# Buzzer.net
KiCad netlist of a schematic drawn in Altium Designer
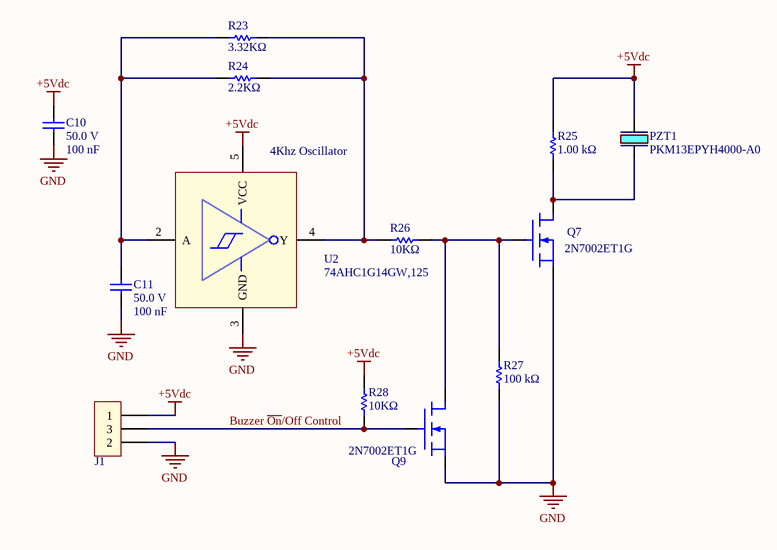
[diagram p0: Buzzer.SchDoc]

(export (version "E")
  (design (tool "Eeschema 10.0.6"))
  (components
    (comp (ref "C10")
      (value "08055C104JAT2A")
      (footprint "Cap,0805")
      (description "Capacitor; Ceramic; Cap 0.1 uF; Tol 5%; Vol-Rtg 50 VDC; SMT; 0805; X7R; Tape & Reel")
      (fields (field (name "VOLTAGE RATING (DC)") "50.0 V") (field (name "CAPACITANCE") "100 nF"))
      (libsource (lib "Master Mar2021") (part "Cap,0805,100nf,50V,5%,08055C104JAT2A"))
    )
    (comp (ref "C11")
      (value "08055C104JAT2A")
      (footprint "Cap,0805")
      (description "Capacitor; Ceramic; Cap 0.1 uF; Tol 5%; Vol-Rtg 50 VDC; SMT; 0805; X7R; Tape & Reel")
      (fields (field (name "VOLTAGE RATING (DC)") "50.0 V") (field (name "CAPACITANCE") "100 nF"))
      (libsource (lib "Master Mar2021") (part "Cap,0805,100nf,50V,5%,08055C104JAT2A"))
    )
    (comp (ref "J1")
      (value "Generic Header")
      (footprint "Header,3POS,0.1\",RA")
      (description "Generic Header 3 pos header 0.1\"")
      (libsource (lib "Master DEC 2020") (part "Header 1x3,0.1{dblquote},TH,Generic"))
    )
    (comp (ref "PZT1")
      (value "PKM13EPYH4000-A0")
      (footprint "Buzzer,PKM13EPYH4000-A0")
      (description "AUDIO PIEZO TRANSDUCER 30V TH")
      (fields (field (name "MANUFACTURER") "Murata Electronics"))
      (libsource (lib "Master Mar2021") (part "Buzzer,PIEZO,30V,TH,4Khz,PKM13EPYH4000-A0"))
    )
    (comp (ref "Q7")
      (value "2N7002ET1G")
      (footprint "SOT23-3")
      (description "Small Signal MOSFET, 60 V, 310 mA, Single, N-Channel, 3-Pin SOT-23, Pb-Free, Tape and Reel")
      (fields
        (field (name "MANUFACTURER") "ON Semiconductor")
        (field (name "MANUFACTURER PART NUMBER") "2N7002ET1G")
      )
      (libsource (lib "Master Mar2021") (part "MOSFET,N-Channel,SOT23,0.25A,60V,2N7002ET1G"))
    )
    (comp (ref "Q9")
      (value "2N7002ET1G")
      (footprint "SOT23-3")
      (description "Small Signal MOSFET, 60 V, 310 mA, Single, N-Channel, 3-Pin SOT-23, Pb-Free, Tape and Reel")
      (fields
        (field (name "MANUFACTURER") "ON Semiconductor")
        (field (name "MANUFACTURER PART NUMBER") "2N7002ET1G")
      )
      (libsource (lib "Master Mar2021") (part "MOSFET,N-Channel,SOT23,0.25A,60V,2N7002ET1G"))
    )
    (comp (ref "R23")
      (value "CRCW08053K32FKEA")
      (footprint "res, 0805, HD")
      (description "RES SMD 3.32K OHM 1% 1/8W 0805")
      (fields (field (name "RESISTANCE") "3.32KΩ"))
      (libsource (lib "Master Mar2021") (part "Res,0805,3.32K,±1%,100.0 ppm/°C,150.0 V,CRCW08053K32FKEA"))
    )
    (comp (ref "R24")
      (value "CRCW08052K20FKEA")
      (footprint "res, 0805, HD")
      (description "RES SMD 2.2K OHM 1% 1/8W 0805")
      (fields (field (name "RESISTANCE") "2.2KΩ"))
      (libsource (lib "Master Mar2021") (part "Res,0805,2.2KΩ,±1%,100.0 ppm/°C,150.0 V,CRCW08052K20FKEA"))
    )
    (comp (ref "R25")
      (value "Vishay CRCW08051K00JNEA")
      (footprint "res, 0805, HD")
      (description "Res Thick Film 0805 1K Ohm 5% 0.125W(1/8W) ±200ppm/C Molded SMD Automotive Paper T/R")
      (fields
        (field (name "MANUFACTURER PART NUMBER") "CRCW08051K00JNEA")
        (field (name "RESISTANCE") "1.00 kΩ")
      )
      (libsource (lib "Master Mar2021") (part "Res,0805,1.00 kΩ,5%,200ppm,CRCW08051K00JNEA"))
    )
    (comp (ref "R26")
      (value "Vishay / Dale CRCW080510K0FKTA")
      (footprint "res, 0805, HD")
      (description "RES SMD 10K OHM 1% 1/8W 0805")
      (fields (field (name "RESISTANCE") "10KΩ"))
      (libsource (lib "Master Mar2021") (part "Res,0805,10.0kΩ,1%,100 ppm,CRCW080510K0FKTA"))
    )
    (comp (ref "R27")
      (value "CRCW0805100KFKEA")
      (footprint "res, 0805, HD")
      (description "100 kOhms ±1% 0.125W, 1/8W Chip Resistor 0805 (2012 Metric) Thick Film")
      (fields (field (name "MANUFACTURER") "Vishay") (field (name "RESISTANCE") "100 kΩ"))
      (libsource (lib "Master Mar2021") (part "Res,0805,100kΩ,1%,100ppm,CRCW0805100KFKEA"))
    )
    (comp (ref "R28")
      (value "Vishay / Dale CRCW080510K0FKTA")
      (footprint "res, 0805, HD")
      (description "RES SMD 10K OHM 1% 1/8W 0805")
      (fields (field (name "RESISTANCE") "10KΩ"))
      (libsource (lib "Master Mar2021") (part "Res,0805,10.0kΩ,1%,100 ppm,CRCW080510K0FKTA"))
    )
    (comp (ref "U2")
      (value "74AHC1G14GW,125")
      (footprint "SOT23-5")
      (description "IC INVERTER SCHMITT 1CH 5TSSOP")
      (fields (field (name "MANUFACTURER") "Nexperia USA Inc."))
      (libsource (lib "Master Mar2021") (part "IC,Logic,Schmitt trigger INV,2V ~ 5.5V,5-TSSOP , 74AHC1G14GW,125"))
    )
  )
  (nets
    (net (code "1") (name "+5Vdc") (class "Default")
      (node (ref "C10") (pin "2") (pinfunction "2_2") (pintype "passive"))
      (node (ref "J1") (pin "1") (pinfunction "1_1") (pintype "passive"))
      (node (ref "PZT1") (pin "2") (pinfunction "2_2") (pintype "passive"))
      (node (ref "R25") (pin "1") (pinfunction "1_1") (pintype "passive"))
      (node (ref "R28") (pin "1") (pinfunction "1_1") (pintype "passive"))
      (node (ref "U2") (pin "5") (pinfunction "VCC_5") (pintype "passive"))
    )
    (net (code "2") (name "/Buzzer ~{On}{slash}Off Control") (class "Default")
      (node (ref "J1") (pin "3") (pinfunction "3_3") (pintype "passive"))
      (node (ref "Q9") (pin "1") (pinfunction "G_1") (pintype "passive"))
      (node (ref "R28") (pin "2") (pinfunction "2_2") (pintype "passive"))
    )
    (net (code "3") (name "GND") (class "Default")
      (node (ref "C10") (pin "1") (pinfunction "1_1") (pintype "passive"))
      (node (ref "C11") (pin "2") (pinfunction "2_2") (pintype "passive"))
      (node (ref "J1") (pin "2") (pinfunction "2_2") (pintype "passive"))
      (node (ref "Q7") (pin "2") (pinfunction "S_2") (pintype "passive"))
      (node (ref "Q9") (pin "2") (pinfunction "S_2") (pintype "passive"))
      (node (ref "R27") (pin "2") (pinfunction "2_2") (pintype "passive"))
      (node (ref "U2") (pin "3") (pinfunction "GND_3") (pintype "passive"))
    )
    (net (code "4") (name "Net-(Q7-D)") (class "Default")
      (node (ref "PZT1") (pin "1") (pinfunction "1_1") (pintype "passive"))
      (node (ref "Q7") (pin "3") (pinfunction "D_3") (pintype "passive"))
      (node (ref "R25") (pin "2") (pinfunction "2_2") (pintype "passive"))
    )
    (net (code "5") (name "Net-(Q7-G)") (class "Default")
      (node (ref "Q7") (pin "1") (pinfunction "G_1") (pintype "passive"))
      (node (ref "Q9") (pin "3") (pinfunction "D_3") (pintype "passive"))
      (node (ref "R26") (pin "1") (pinfunction "1_1") (pintype "passive"))
      (node (ref "R27") (pin "1") (pinfunction "1_1") (pintype "passive"))
    )
    (net (code "6") (name "Net-(U2-A)") (class "Default")
      (node (ref "C11") (pin "1") (pinfunction "1_1") (pintype "passive"))
      (node (ref "R23") (pin "2") (pinfunction "2_2") (pintype "passive"))
      (node (ref "R24") (pin "2") (pinfunction "2_2") (pintype "passive"))
      (node (ref "U2") (pin "2") (pinfunction "A_2") (pintype "passive"))
    )
    (net (code "7") (name "Net-(U2-Y)") (class "Default")
      (node (ref "R23") (pin "1") (pinfunction "1_1") (pintype "passive"))
      (node (ref "R24") (pin "1") (pinfunction "1_1") (pintype "passive"))
      (node (ref "R26") (pin "2") (pinfunction "2_2") (pintype "passive"))
      (node (ref "U2") (pin "4") (pinfunction "Y_4") (pintype "passive"))
    )
    (net (code "8") (name "unconnected-(U2-N{slash}C-Pad1)") (class "Default")
      (node (ref "U2") (pin "1") (pinfunction "N/C_1") (pintype "passive"))
    )
  )
)
